# nguon.net
KiCad netlist of a schematic drawn in Altium Designer
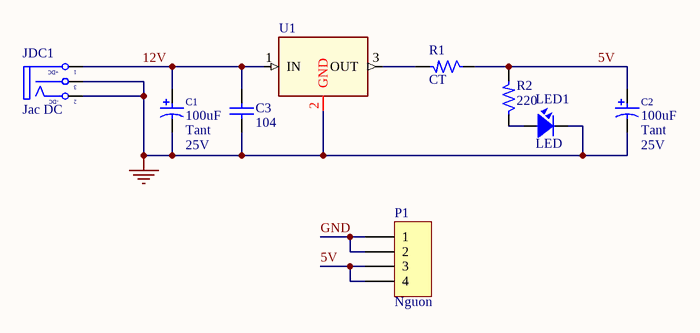
[diagram p0: nguon.SchDoc]

(export (version "E")
  (design (tool "Eeschema 10.0.6"))
  (components
    (comp (ref "C1")
      (value "100uF")
      (footprint "RADIAL B")
      (description "Polarized Capacitor")
      (fields
        (field (name "MANUFACTURER") "FARNELL")
        (field (name "CAPACITOR TYPE") "Tant")
        (field (name "VOLT") "25V")
        (field (name "PUBLISHER") "Hoang Nguyen")
      )
      (libsource (lib "hphonglib") (part "Cap_Pol"))
    )
    (comp (ref "C2")
      (value "100uF")
      (footprint "RADIAL B")
      (description "Polarized Capacitor")
      (fields
        (field (name "MANUFACTURER") "FARNELL")
        (field (name "CAPACITOR TYPE") "Tant")
        (field (name "VOLT") "25V")
        (field (name "PUBLISHER") "Hoang Nguyen")
      )
      (libsource (lib "hphonglib") (part "Cap_Pol"))
    )
    (comp (ref "C3")
      (value "104")
      (footprint "Tu-pico")
      (description "Capacitor")
      (fields (field (name "Comment") "Capacitor Ceramic") (field (name "PUBLISHER") "Altium Limited"))
      (libsource (lib "My Library") (part "CapCeramic"))
    )
    (comp (ref "JDC1")
      (value "Jac DC")
      (footprint "DC0")
      (description "Jac DC input")
      (libsource (lib "Library") (part "DCIN"))
    )
    (comp (ref "LED1")
      (value "LED")
      (footprint "LED-5-RED")
      (description "LED Single colour Green and Red")
      (libsource (lib "syhaunguyen") (part "LED"))
    )
    (comp (ref "P1")
      (value "Nguon")
      (footprint "MinhTien_PCBLib:JST-XH_B4B-XH-A")
      (libsource (lib "MinhTien_SCHLib") (part "Connector_4pin"))
    )
    (comp (ref "R1")
      (value "CT")
      (footprint "R1/8W")
      (description "Resistor 1/4W")
      (libsource (lib "My Library") (part "R"))
    )
    (comp (ref "R2")
      (value "220")
      (footprint "R1/8W")
      (description "Resistor 1/4W")
      (libsource (lib "My Library") (part "R"))
    )
    (comp (ref "U1")
      (value "LM78xx")
      (footprint "TO-220")
      (description "Regulator")
      (fields
        (field (name "MANUFACTURER") "Fairchild Semiconductor Corporation")
        (field (name "TOLERANCE") "4 %")
        (field (name "PUBLISHER") "Hoang Nguyen")
      )
      (libsource (lib "hphonglib") (part "LM78xx"))
    )
  )
  (nets
    (net (code "1") (name "/5V") (class "Default")
      (node (ref "C2") (pin "1") (pinfunction "1_1") (pintype "passive"))
      (node (ref "P1") (pin "3") (pinfunction "3_3") (pintype "passive"))
      (node (ref "P1") (pin "4") (pinfunction "4_4") (pintype "passive"))
      (node (ref "R1") (pin "1") (pinfunction "1_1") (pintype "passive"))
      (node (ref "R2") (pin "2") (pinfunction "2_2") (pintype "passive"))
    )
    (net (code "2") (name "/12V") (class "Default")
      (node (ref "C1") (pin "1") (pinfunction "1_1") (pintype "passive"))
      (node (ref "C3") (pin "2") (pinfunction "2_2") (pintype "passive"))
      (node (ref "JDC1") (pin "1") (pinfunction "T_1") (pintype "passive"))
      (node (ref "U1") (pin "1") (pinfunction "IN_1") (pintype "input"))
    )
    (net (code "3") (name "GND") (class "Default")
      (node (ref "C1") (pin "2") (pinfunction "2_2") (pintype "passive"))
      (node (ref "C2") (pin "2") (pinfunction "2_2") (pintype "passive"))
      (node (ref "C3") (pin "1") (pinfunction "1_1") (pintype "passive"))
      (node (ref "JDC1") (pin "2") (pinfunction "TN_2") (pintype "passive"))
      (node (ref "JDC1") (pin "3") (pinfunction "S_3") (pintype "power_in"))
      (node (ref "LED1") (pin "2") (pinfunction "2_2") (pintype "passive"))
      (node (ref "P1") (pin "1") (pinfunction "1_1") (pintype "passive"))
      (node (ref "P1") (pin "2") (pinfunction "2_2") (pintype "passive"))
      (node (ref "U1") (pin "2") (pinfunction "GND_2") (pintype "power_in"))
    )
    (net (code "4") (name "Net-(LED1-Pad1)") (class "Default")
      (node (ref "LED1") (pin "1") (pinfunction "1_1") (pintype "passive"))
      (node (ref "R2") (pin "1") (pinfunction "1_1") (pintype "passive"))
    )
    (net (code "5") (name "Net-(U1-OUT)") (class "Default")
      (node (ref "R1") (pin "2") (pinfunction "2_2") (pintype "passive"))
      (node (ref "U1") (pin "3") (pinfunction "OUT_3") (pintype "output"))
    )
  )
)
